# IR-BlueDM-MLX90620_Kit.net
KiCad netlist of a schematic drawn in EAGLE
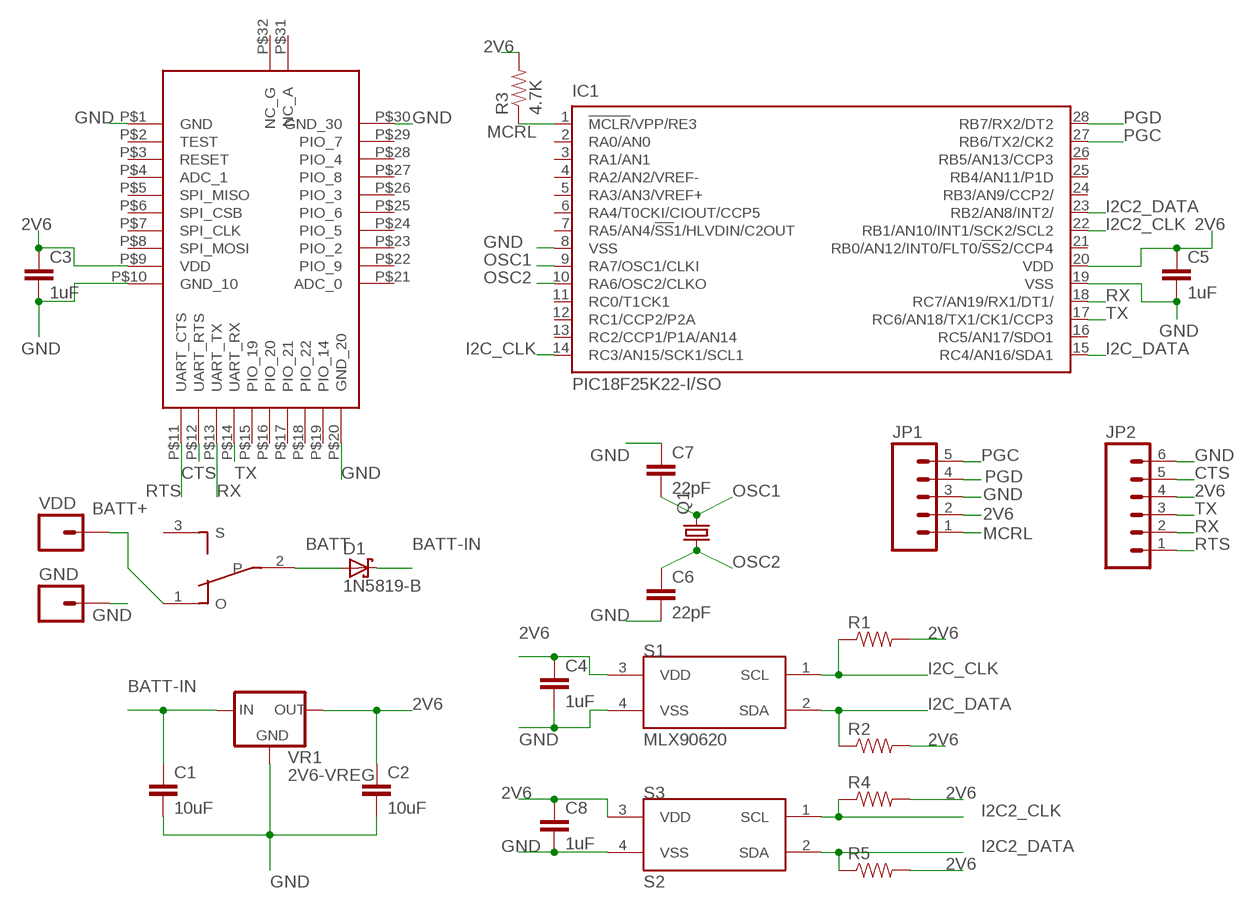
[diagram p0: schematic, sheet 1]

(export (version "E")
  (design (tool "Eeschema 10.0.6"))
  (components
    (comp (ref "C1")
      (value "10uF")
      (footprint "eagle-import:CAP-PTH-5MM")
      (libsource (lib "eagle-import") (part "CAPPTH1"))
    )
    (comp (ref "C2")
      (value "10uF")
      (footprint "eagle-import:CAP-PTH-5MM")
      (libsource (lib "eagle-import") (part "CAPPTH1"))
    )
    (comp (ref "C3")
      (value "1uF")
      (footprint "eagle-import:CAP-PTH-5MM")
      (libsource (lib "eagle-import") (part "CAPPTH1"))
    )
    (comp (ref "C4")
      (value "1uF")
      (footprint "eagle-import:CAP-PTH-5MM")
      (libsource (lib "eagle-import") (part "CAPPTH1"))
    )
    (comp (ref "C5")
      (value "1uF")
      (footprint "eagle-import:CAP-PTH-5MM")
      (libsource (lib "eagle-import") (part "CAPPTH1"))
    )
    (comp (ref "C6")
      (value "22pF")
      (footprint "eagle-import:CAP-PTH-5MM")
      (libsource (lib "eagle-import") (part "CAPPTH1"))
    )
    (comp (ref "C7")
      (value "22pF")
      (footprint "eagle-import:CAP-PTH-5MM")
      (libsource (lib "eagle-import") (part "CAPPTH1"))
    )
    (comp (ref "C8")
      (value "1uF")
      (footprint "eagle-import:CAP-PTH-5MM")
      (libsource (lib "eagle-import") (part "CAPPTH1"))
    )
    (comp (ref "D1")
      (value "1N5819-B")
      (footprint "eagle-import:DO41-7.6")
      (libsource (lib "eagle-import") (part "1N5819-B"))
    )
    (comp (ref "GND")
      (value "M01PTH")
      (footprint "eagle-import:1X01")
      (libsource (lib "eagle-import") (part "M01PTH"))
    )
    (comp (ref "IC1")
      (value "PIC18F25K22-I/SO")
      (footprint "eagle-import:SO28W")
      (libsource (lib "eagle-import") (part "PIC18F25K22/SO-I"))
    )
    (comp (ref "IC2")
      (value "BR-LE4.0-D2A")
      (footprint "eagle-import:BR-LE4.0-X2A")
      (libsource (lib "eagle-import") (part "BR-LE4.0-D2A"))
    )
    (comp (ref "JP1")
      (value "M05PTH")
      (footprint "eagle-import:1X05")
      (libsource (lib "eagle-import") (part "M05PTH"))
    )
    (comp (ref "JP2")
      (value "M06SIP")
      (footprint "eagle-import:1X06")
      (libsource (lib "eagle-import") (part "M06SIP"))
    )
    (comp (ref "Q1")
      (value "CRYSTALHC49S")
      (footprint "eagle-import:HC49_S")
      (libsource (lib "eagle-import") (part "CRYSTALHC49S"))
    )
    (comp (ref "R1")
      (value "RESISTORPTH-1/4W")
      (footprint "eagle-import:AXIAL-0.4")
      (libsource (lib "eagle-import") (part "RESISTORPTH-1/4W"))
    )
    (comp (ref "R2")
      (value "RESISTORPTH-1/4W")
      (footprint "eagle-import:AXIAL-0.4")
      (libsource (lib "eagle-import") (part "RESISTORPTH-1/4W"))
    )
    (comp (ref "R3")
      (value "4.7K")
      (footprint "eagle-import:AXIAL-0.4")
      (libsource (lib "eagle-import") (part "RESISTORPTH-1/4W"))
    )
    (comp (ref "R4")
      (value "RESISTORPTH-1/4W")
      (footprint "eagle-import:AXIAL-0.4")
      (libsource (lib "eagle-import") (part "RESISTORPTH-1/4W"))
    )
    (comp (ref "R5")
      (value "RESISTORPTH-1/4W")
      (footprint "eagle-import:AXIAL-0.4")
      (libsource (lib "eagle-import") (part "RESISTORPTH-1/4W"))
    )
    (comp (ref "S1")
      (value "MLX90620")
      (footprint "eagle-import:TO-39")
      (libsource (lib "eagle-import") (part "MLX90620"))
    )
    (comp (ref "S2")
      (value "SMALL_SWITCH")
      (footprint "eagle-import:EG1213")
      (libsource (lib "eagle-import") (part "SMALL_SWITCH"))
    )
    (comp (ref "S3")
      (value "S2")
      (footprint "eagle-import:TO-39")
      (libsource (lib "eagle-import") (part "MLX90620"))
    )
    (comp (ref "VDD")
      (value "M01PTH")
      (footprint "eagle-import:1X01")
      (libsource (lib "eagle-import") (part "M01PTH"))
    )
    (comp (ref "VR1")
      (value "2V6-VREG")
      (footprint "eagle-import:TO-92")
      (libsource (lib "eagle-import") (part "2V6-VREG"))
    )
  )
  (nets
    (net (code "1") (name "/2V6") (class "Default")
      (node (ref "C2") (pin "1") (pinfunction "1_1") (pintype "passive"))
      (node (ref "C3") (pin "1") (pinfunction "1_1") (pintype "passive"))
      (node (ref "C4") (pin "1") (pinfunction "1_1") (pintype "passive"))
      (node (ref "C5") (pin "1") (pinfunction "1_1") (pintype "passive"))
      (node (ref "C8") (pin "1") (pinfunction "1_1") (pintype "passive"))
      (node (ref "IC1") (pin "20") (pinfunction "VDD_20") (pintype "power_in"))
      (node (ref "IC2") (pin "P$9") (pinfunction "VDD_P$9") (pintype "power_in"))
      (node (ref "JP1") (pin "2") (pinfunction "2_2") (pintype "passive"))
      (node (ref "JP2") (pin "4") (pinfunction "4_4") (pintype "passive"))
      (node (ref "R1") (pin "P$2") (pinfunction "2_P$2") (pintype "passive"))
      (node (ref "R2") (pin "P$2") (pinfunction "2_P$2") (pintype "passive"))
      (node (ref "R3") (pin "P$2") (pinfunction "2_P$2") (pintype "passive"))
      (node (ref "R4") (pin "P$2") (pinfunction "2_P$2") (pintype "passive"))
      (node (ref "R5") (pin "P$2") (pinfunction "2_P$2") (pintype "passive"))
      (node (ref "S1") (pin "3") (pinfunction "VDD_3") (pintype "bidirectional"))
      (node (ref "S3") (pin "3") (pinfunction "VDD_3") (pintype "bidirectional"))
      (node (ref "VR1") (pin "1") (pinfunction "OUT_1") (pintype "output"))
    )
    (net (code "2") (name "/BATT") (class "Default")
      (node (ref "D1") (pin "A") (pinfunction "A_A") (pintype "passive"))
      (node (ref "S2") (pin "2") (pinfunction "P_2") (pintype "bidirectional"))
    )
    (net (code "3") (name "/BATT+") (class "Default")
      (node (ref "S2") (pin "1") (pinfunction "O_1") (pintype "bidirectional"))
      (node (ref "VDD") (pin "1") (pinfunction "1_1") (pintype "passive"))
    )
    (net (code "4") (name "/BATT-IN") (class "Default")
      (node (ref "C1") (pin "1") (pinfunction "1_1") (pintype "passive"))
      (node (ref "D1") (pin "C") (pinfunction "C_C") (pintype "passive"))
      (node (ref "VR1") (pin "3") (pinfunction "IN_3") (pintype "input"))
    )
    (net (code "5") (name "/CTS") (class "Default")
      (node (ref "IC2") (pin "P$12") (pinfunction "UART_RTS_P$12") (pintype "bidirectional"))
      (node (ref "JP2") (pin "5") (pinfunction "5_5") (pintype "passive"))
    )
    (net (code "6") (name "/GND") (class "Default")
      (node (ref "C1") (pin "2") (pinfunction "2_2") (pintype "passive"))
      (node (ref "C2") (pin "2") (pinfunction "2_2") (pintype "passive"))
      (node (ref "C3") (pin "2") (pinfunction "2_2") (pintype "passive"))
      (node (ref "C4") (pin "2") (pinfunction "2_2") (pintype "passive"))
      (node (ref "C5") (pin "2") (pinfunction "2_2") (pintype "passive"))
      (node (ref "C6") (pin "2") (pinfunction "2_2") (pintype "passive"))
      (node (ref "C7") (pin "1") (pinfunction "1_1") (pintype "passive"))
      (node (ref "C8") (pin "2") (pinfunction "2_2") (pintype "passive"))
      (node (ref "GND") (pin "1") (pinfunction "1_1") (pintype "passive"))
      (node (ref "IC1") (pin "19") (pinfunction "VSS_19") (pintype "power_in"))
      (node (ref "IC1") (pin "8") (pinfunction "VSS_8") (pintype "power_in"))
      (node (ref "IC2") (pin "P$1") (pinfunction "GND_P$1") (pintype "power_in"))
      (node (ref "IC2") (pin "P$10") (pinfunction "GND_10_P$10") (pintype "power_in"))
      (node (ref "IC2") (pin "P$20") (pinfunction "GND_20_P$20") (pintype "power_in"))
      (node (ref "IC2") (pin "P$30") (pinfunction "GND_30_P$30") (pintype "power_in"))
      (node (ref "JP1") (pin "3") (pinfunction "3_3") (pintype "passive"))
      (node (ref "JP2") (pin "6") (pinfunction "6_6") (pintype "passive"))
      (node (ref "S1") (pin "4") (pinfunction "VSS_4") (pintype "bidirectional"))
      (node (ref "S3") (pin "4") (pinfunction "VSS_4") (pintype "bidirectional"))
      (node (ref "VR1") (pin "2") (pinfunction "GND_2") (pintype "input"))
    )
    (net (code "7") (name "/I2C2_CLK") (class "Default")
      (node (ref "IC1") (pin "22") (pinfunction "RB1/AN10/INT1/SCK2/SCL2_22") (pintype "bidirectional"))
      (node (ref "R4") (pin "P$1") (pinfunction "1_P$1") (pintype "passive"))
      (node (ref "S3") (pin "1") (pinfunction "SCL_1") (pintype "bidirectional"))
    )
    (net (code "8") (name "/I2C2_DATA") (class "Default")
      (node (ref "IC1") (pin "23") (pinfunction "RB2/AN8/INT2/_23") (pintype "bidirectional"))
      (node (ref "R5") (pin "P$1") (pinfunction "1_P$1") (pintype "passive"))
      (node (ref "S3") (pin "2") (pinfunction "SDA_2") (pintype "bidirectional"))
    )
    (net (code "9") (name "/I2C_CLK") (class "Default")
      (node (ref "IC1") (pin "14") (pinfunction "RC3/AN15/SCK1/SCL1_14") (pintype "bidirectional"))
      (node (ref "R1") (pin "P$1") (pinfunction "1_P$1") (pintype "passive"))
      (node (ref "S1") (pin "1") (pinfunction "SCL_1") (pintype "bidirectional"))
    )
    (net (code "10") (name "/I2C_DATA") (class "Default")
      (node (ref "IC1") (pin "15") (pinfunction "RC4/AN16/SDA1_15") (pintype "bidirectional"))
      (node (ref "R2") (pin "P$1") (pinfunction "1_P$1") (pintype "passive"))
      (node (ref "S1") (pin "2") (pinfunction "SDA_2") (pintype "bidirectional"))
    )
    (net (code "11") (name "/MCRL") (class "Default")
      (node (ref "IC1") (pin "1") (pinfunction "~{MCLR}/VPP/RE3_1") (pintype "input"))
      (node (ref "JP1") (pin "1") (pinfunction "1_1") (pintype "passive"))
      (node (ref "R3") (pin "P$1") (pinfunction "1_P$1") (pintype "passive"))
    )
    (net (code "12") (name "/OSC1") (class "Default")
      (node (ref "C7") (pin "2") (pinfunction "2_2") (pintype "passive"))
      (node (ref "IC1") (pin "9") (pinfunction "RA7/OSC1/CLKI_9") (pintype "input"))
      (node (ref "Q1") (pin "2") (pinfunction "2_2") (pintype "passive"))
    )
    (net (code "13") (name "/OSC2") (class "Default")
      (node (ref "C6") (pin "1") (pinfunction "1_1") (pintype "passive"))
      (node (ref "IC1") (pin "10") (pinfunction "RA6/OSC2/CLKO_10") (pintype "output"))
      (node (ref "Q1") (pin "1") (pinfunction "1_1") (pintype "passive"))
    )
    (net (code "14") (name "/PGC") (class "Default")
      (node (ref "IC1") (pin "27") (pinfunction "RB6/TX2/CK2_27") (pintype "bidirectional"))
      (node (ref "JP1") (pin "5") (pinfunction "5_5") (pintype "passive"))
    )
    (net (code "15") (name "/PGD") (class "Default")
      (node (ref "IC1") (pin "28") (pinfunction "RB7/RX2/DT2_28") (pintype "bidirectional"))
      (node (ref "JP1") (pin "4") (pinfunction "4_4") (pintype "passive"))
    )
    (net (code "16") (name "/RTS") (class "Default")
      (node (ref "IC2") (pin "P$11") (pinfunction "UART_CTS_P$11") (pintype "bidirectional"))
      (node (ref "JP2") (pin "1") (pinfunction "1_1") (pintype "passive"))
    )
    (net (code "17") (name "/RX") (class "Default")
      (node (ref "IC1") (pin "18") (pinfunction "RC7/AN19/RX1/DT1/_18") (pintype "bidirectional"))
      (node (ref "IC2") (pin "P$13") (pinfunction "UART_TX_P$13") (pintype "bidirectional"))
      (node (ref "JP2") (pin "2") (pinfunction "2_2") (pintype "passive"))
    )
    (net (code "18") (name "/TX") (class "Default")
      (node (ref "IC1") (pin "17") (pinfunction "RC6/AN18/TX1/CK1/CCP3_17") (pintype "bidirectional"))
      (node (ref "IC2") (pin "P$14") (pinfunction "UART_RX_P$14") (pintype "bidirectional"))
      (node (ref "JP2") (pin "3") (pinfunction "3_3") (pintype "passive"))
    )
    (net (code "19") (name "unconnected-(IC1-RA0{slash}AN0-Pad2)") (class "Default")
      (node (ref "IC1") (pin "2") (pinfunction "RA0/AN0_2") (pintype "bidirectional"))
    )
    (net (code "20") (name "unconnected-(IC1-RA1{slash}AN1-Pad3)") (class "Default")
      (node (ref "IC1") (pin "3") (pinfunction "RA1/AN1_3") (pintype "bidirectional"))
    )
    (net (code "21") (name "unconnected-(IC1-RA2{slash}AN2{slash}VREF--Pad4)") (class "Default")
      (node (ref "IC1") (pin "4") (pinfunction "RA2/AN2/VREF-_4") (pintype "bidirectional"))
    )
    (net (code "22") (name "unconnected-(IC1-RA3{slash}AN3{slash}VREF+-Pad5)") (class "Default")
      (node (ref "IC1") (pin "5") (pinfunction "RA3/AN3/VREF+_5") (pintype "bidirectional"))
    )
    (net (code "23") (name "unconnected-(IC1-RA4{slash}T0CKI{slash}CIOUT{slash}CCP5-Pad6)") (class "Default")
      (node (ref "IC1") (pin "6") (pinfunction "RA4/T0CKI/CIOUT/CCP5_6") (pintype "bidirectional"))
    )
    (net (code "24") (name "unconnected-(IC1-RA5{slash}AN4{slash}~{SS}1{slash}HLVDIN{slash}C2OUT-Pad7)") (class "Default")
      (node (ref "IC1") (pin "7") (pinfunction "RA5/AN4/~{SS}1/HLVDIN/C2OUT_7") (pintype "bidirectional"))
    )
    (net (code "25") (name "unconnected-(IC1-RB0{slash}AN12{slash}INT0{slash}FLT0{slash}~{SS}2{slash}CCP4-Pad21)") (class "Default")
      (node (ref "IC1") (pin "21") (pinfunction "RB0/AN12/INT0/FLT0/~{SS}2/CCP4_21") (pintype "bidirectional"))
    )
    (net (code "26") (name "unconnected-(IC1-RB3{slash}AN9{slash}CCP2{slash}-Pad24)") (class "Default")
      (node (ref "IC1") (pin "24") (pinfunction "RB3/AN9/CCP2/_24") (pintype "bidirectional"))
    )
    (net (code "27") (name "unconnected-(IC1-RB4{slash}AN11{slash}P1D-Pad25)") (class "Default")
      (node (ref "IC1") (pin "25") (pinfunction "RB4/AN11/P1D_25") (pintype "bidirectional"))
    )
    (net (code "28") (name "unconnected-(IC1-RB5{slash}AN13{slash}CCP3-Pad26)") (class "Default")
      (node (ref "IC1") (pin "26") (pinfunction "RB5/AN13/CCP3_26") (pintype "bidirectional"))
    )
    (net (code "29") (name "unconnected-(IC1-RC0{slash}T1CK1-Pad11)") (class "Default")
      (node (ref "IC1") (pin "11") (pinfunction "RC0/T1CK1_11") (pintype "bidirectional"))
    )
    (net (code "30") (name "unconnected-(IC1-RC1{slash}CCP2{slash}P2A-Pad12)") (class "Default")
      (node (ref "IC1") (pin "12") (pinfunction "RC1/CCP2/P2A_12") (pintype "bidirectional"))
    )
    (net (code "31") (name "unconnected-(IC1-RC2{slash}CCP1{slash}P1A{slash}AN14-Pad13)") (class "Default")
      (node (ref "IC1") (pin "13") (pinfunction "RC2/CCP1/P1A/AN14_13") (pintype "bidirectional"))
    )
    (net (code "32") (name "unconnected-(IC1-RC5{slash}AN17{slash}SDO1-Pad16)") (class "Default")
      (node (ref "IC1") (pin "16") (pinfunction "RC5/AN17/SDO1_16") (pintype "bidirectional"))
    )
    (net (code "33") (name "unconnected-(IC2-ADC_0-PadP$21)") (class "Default")
      (node (ref "IC2") (pin "P$21") (pinfunction "ADC_0_P$21") (pintype "bidirectional"))
    )
    (net (code "34") (name "unconnected-(IC2-ADC_1-PadP$4)") (class "Default")
      (node (ref "IC2") (pin "P$4") (pinfunction "ADC_1_P$4") (pintype "bidirectional"))
    )
    (net (code "35") (name "unconnected-(IC2-NC_A-PadP$31)") (class "Default")
      (node (ref "IC2") (pin "P$31") (pinfunction "NC_A_P$31") (pintype "no_connect"))
    )
    (net (code "36") (name "unconnected-(IC2-NC_G-PadP$32)") (class "Default")
      (node (ref "IC2") (pin "P$32") (pinfunction "NC_G_P$32") (pintype "no_connect"))
    )
    (net (code "37") (name "unconnected-(IC2-PIO_2-PadP$23)") (class "Default")
      (node (ref "IC2") (pin "P$23") (pinfunction "PIO_2_P$23") (pintype "bidirectional"))
    )
    (net (code "38") (name "unconnected-(IC2-PIO_3-PadP$26)") (class "Default")
      (node (ref "IC2") (pin "P$26") (pinfunction "PIO_3_P$26") (pintype "bidirectional"))
    )
    (net (code "39") (name "unconnected-(IC2-PIO_4-PadP$28)") (class "Default")
      (node (ref "IC2") (pin "P$28") (pinfunction "PIO_4_P$28") (pintype "bidirectional"))
    )
    (net (code "40") (name "unconnected-(IC2-PIO_5-PadP$24)") (class "Default")
      (node (ref "IC2") (pin "P$24") (pinfunction "PIO_5_P$24") (pintype "bidirectional"))
    )
    (net (code "41") (name "unconnected-(IC2-PIO_6-PadP$25)") (class "Default")
      (node (ref "IC2") (pin "P$25") (pinfunction "PIO_6_P$25") (pintype "bidirectional"))
    )
    (net (code "42") (name "unconnected-(IC2-PIO_7-PadP$29)") (class "Default")
      (node (ref "IC2") (pin "P$29") (pinfunction "PIO_7_P$29") (pintype "bidirectional"))
    )
    (net (code "43") (name "unconnected-(IC2-PIO_8-PadP$27)") (class "Default")
      (node (ref "IC2") (pin "P$27") (pinfunction "PIO_8_P$27") (pintype "bidirectional"))
    )
    (net (code "44") (name "unconnected-(IC2-PIO_9-PadP$22)") (class "Default")
      (node (ref "IC2") (pin "P$22") (pinfunction "PIO_9_P$22") (pintype "bidirectional"))
    )
    (net (code "45") (name "unconnected-(IC2-PIO_14-PadP$19)") (class "Default")
      (node (ref "IC2") (pin "P$19") (pinfunction "PIO_14_P$19") (pintype "bidirectional"))
    )
    (net (code "46") (name "unconnected-(IC2-PIO_19-PadP$15)") (class "Default")
      (node (ref "IC2") (pin "P$15") (pinfunction "PIO_19_P$15") (pintype "bidirectional"))
    )
    (net (code "47") (name "unconnected-(IC2-PIO_20-PadP$16)") (class "Default")
      (node (ref "IC2") (pin "P$16") (pinfunction "PIO_20_P$16") (pintype "bidirectional"))
    )
    (net (code "48") (name "unconnected-(IC2-PIO_21-PadP$17)") (class "Default")
      (node (ref "IC2") (pin "P$17") (pinfunction "PIO_21_P$17") (pintype "bidirectional"))
    )
    (net (code "49") (name "unconnected-(IC2-PIO_22-PadP$18)") (class "Default")
      (node (ref "IC2") (pin "P$18") (pinfunction "PIO_22_P$18") (pintype "bidirectional"))
    )
    (net (code "50") (name "unconnected-(IC2-RESET-PadP$3)") (class "Default")
      (node (ref "IC2") (pin "P$3") (pinfunction "RESET_P$3") (pintype "bidirectional"))
    )
    (net (code "51") (name "unconnected-(IC2-SPI_CLK-PadP$7)") (class "Default")
      (node (ref "IC2") (pin "P$7") (pinfunction "SPI_CLK_P$7") (pintype "bidirectional"))
    )
    (net (code "52") (name "unconnected-(IC2-SPI_CSB-PadP$6)") (class "Default")
      (node (ref "IC2") (pin "P$6") (pinfunction "SPI_CSB_P$6") (pintype "bidirectional"))
    )
    (net (code "53") (name "unconnected-(IC2-SPI_MISO-PadP$5)") (class "Default")
      (node (ref "IC2") (pin "P$5") (pinfunction "SPI_MISO_P$5") (pintype "bidirectional"))
    )
    (net (code "54") (name "unconnected-(IC2-SPI_MOSI-PadP$8)") (class "Default")
      (node (ref "IC2") (pin "P$8") (pinfunction "SPI_MOSI_P$8") (pintype "bidirectional"))
    )
    (net (code "55") (name "unconnected-(IC2-TEST-PadP$2)") (class "Default")
      (node (ref "IC2") (pin "P$2") (pinfunction "TEST_P$2") (pintype "bidirectional"))
    )
    (net (code "56") (name "unconnected-(S2-S-Pad3)") (class "Default")
      (node (ref "S2") (pin "3") (pinfunction "S_3") (pintype "bidirectional"))
    )
  )
)
